# Classic-Narrow-5V-SIDE-USB.net
KiCad netlist of a schematic drawn in EAGLE
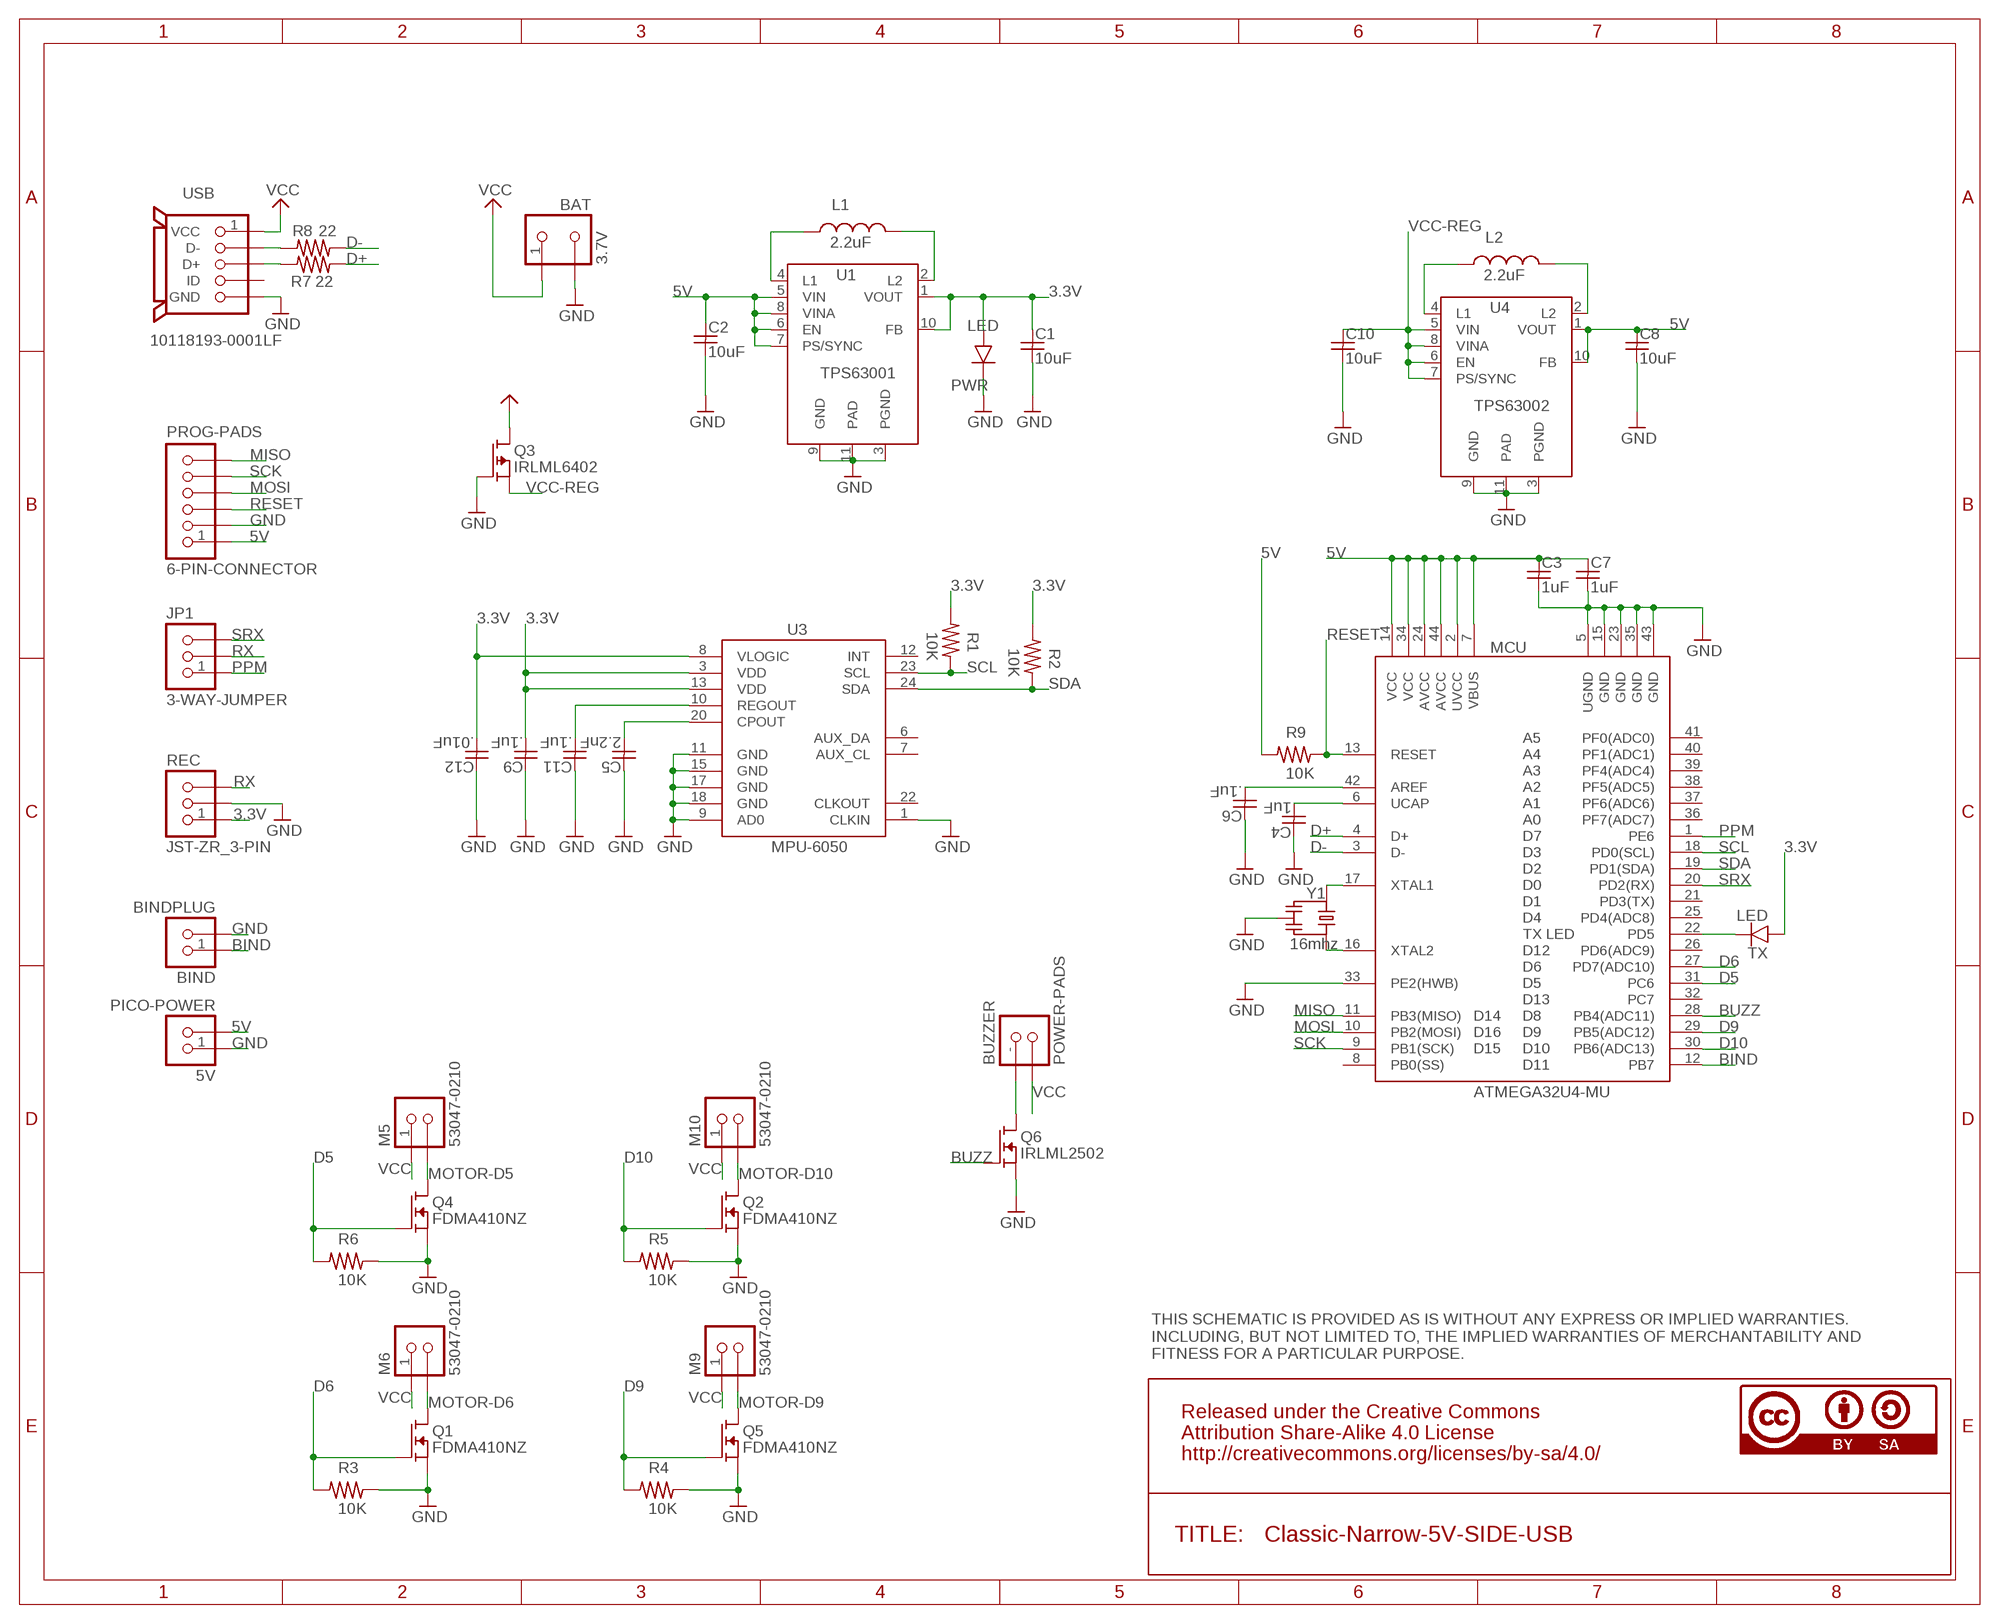
[diagram p0: schematic, sheet 1]

(export (version "E")
  (design (tool "Eeschema 10.0.6"))
  (components
    (comp (ref "5V")
      (value "PICO-POWER")
      (footprint "eagle-import:PICO_1.25_.5MM")
      (fields (field (name "MF") "Molex") (field (name "MPN") "53047-0210"))
      (libsource (lib "eagle-import") (part "PICO-POWER"))
    )
    (comp (ref "BAT")
      (value "3.7V")
      (footprint "eagle-import:S2B-PH-K-S")
      (fields (field (name "MF") "JST") (field (name "MPN") "S2B-PH-K-S"))
      (libsource (lib "eagle-import") (part "JST-PH-BAT"))
    )
    (comp (ref "BIND")
      (value "BINDPLUG")
      (footprint "eagle-import:B3U-1000P(M)")
      (fields (field (name "MF") "Omron") (field (name "MPN") "B3U-1000P"))
      (libsource (lib "eagle-import") (part "TACTILE-SWITCH"))
    )
    (comp (ref "BUZZER")
      (value "POWER-PADS")
      (footprint "eagle-import:POW-PADS")
      (libsource (lib "eagle-import") (part "POWER-PADS"))
    )
    (comp (ref "C1")
      (value "10uF")
      (footprint "eagle-import:YUDEN-CAP-0805")
      (fields (field (name "MF") "Taiyo Yuden") (field (name "MPN") "JMK212AB7106KG-T"))
      (libsource (lib "eagle-import") (part "CAPACITOR10UF"))
    )
    (comp (ref "C2")
      (value "10uF")
      (footprint "eagle-import:YUDEN-CAP-0805")
      (fields (field (name "MF") "Taiyo Yuden") (field (name "MPN") "JMK212AB7106KG-T"))
      (libsource (lib "eagle-import") (part "CAPACITOR10UF"))
    )
    (comp (ref "C3")
      (value "1uF")
      (footprint "eagle-import:MUR-CAP-0603")
      (fields (field (name "MF") "Murata") (field (name "MPN") "GRM188R71C105KA12D"))
      (libsource (lib "eagle-import") (part "CAPACITOR1UF"))
    )
    (comp (ref "C4")
      (value "1uF")
      (footprint "eagle-import:MUR-CAP-0603")
      (fields (field (name "MF") "Murata") (field (name "MPN") "GRM188R71C105KA12D"))
      (libsource (lib "eagle-import") (part "CAPACITOR1UF"))
    )
    (comp (ref "C5")
      (value "2.2nF")
      (footprint "eagle-import:MUR-CAP-0603")
      (fields (field (name "MF") "Murata") (field (name "MPN") "GRM188R71C222KA01D"))
      (libsource (lib "eagle-import") (part "CAPACITOR2.2NF"))
    )
    (comp (ref "C6")
      (value ".1uF")
      (footprint "eagle-import:MUR-CAP-0603")
      (fields (field (name "MF") "Murata") (field (name "MPN") "GRM188R71C104KA01D"))
      (libsource (lib "eagle-import") (part "CAPACITOR.1UF"))
    )
    (comp (ref "C7")
      (value "1uF")
      (footprint "eagle-import:MUR-CAP-0603")
      (fields (field (name "MF") "Murata") (field (name "MPN") "GRM188R71C105KA12D"))
      (libsource (lib "eagle-import") (part "CAPACITOR1UF"))
    )
    (comp (ref "C8")
      (value "10uF")
      (footprint "eagle-import:YUDEN-CAP-0805")
      (fields (field (name "MF") "Taiyo Yuden") (field (name "MPN") "JMK212AB7106KG-T"))
      (libsource (lib "eagle-import") (part "CAPACITOR10UF"))
    )
    (comp (ref "C9")
      (value ".1uF")
      (footprint "eagle-import:MUR-CAP-0603")
      (fields (field (name "MF") "Murata") (field (name "MPN") "GRM188R71C104KA01D"))
      (libsource (lib "eagle-import") (part "CAPACITOR.1UF"))
    )
    (comp (ref "C10")
      (value "10uF")
      (footprint "eagle-import:YUDEN-CAP-0805")
      (fields (field (name "MF") "Taiyo Yuden") (field (name "MPN") "JMK212AB7106KG-T"))
      (libsource (lib "eagle-import") (part "CAPACITOR10UF"))
    )
    (comp (ref "C11")
      (value ".1uF")
      (footprint "eagle-import:MUR-CAP-0603")
      (fields (field (name "MF") "Murata") (field (name "MPN") "GRM188R71C104KA01D"))
      (libsource (lib "eagle-import") (part "CAPACITOR.1UF"))
    )
    (comp (ref "C12")
      (value ".01uF")
      (footprint "eagle-import:MUR-CAP-0603")
      (fields (field (name "MF") "Murata") (field (name "MPN") "GRM188R71C103KA01D"))
      (libsource (lib "eagle-import") (part "CAPACITOR.01UF"))
    )
    (comp (ref "JP1")
      (value "3-WAY-JUMPER")
      (footprint "eagle-import:3-WAY-JUMPER")
      (libsource (lib "eagle-import") (part "3-WAY-JUMPER"))
    )
    (comp (ref "L1")
      (value "2.2uF")
      (footprint "eagle-import:NR301X")
      (fields (field (name "MF") "Taiyo Yuden") (field (name "MPN") "NR3015T2R2M"))
      (libsource (lib "eagle-import") (part "NR301X"))
    )
    (comp (ref "L2")
      (value "2.2uF")
      (footprint "eagle-import:NR301X")
      (fields (field (name "MF") "Taiyo Yuden") (field (name "MPN") "NR3015T2R2M"))
      (libsource (lib "eagle-import") (part "NR301X"))
    )
    (comp (ref "M5")
      (value "53047-0210")
      (footprint "eagle-import:PICO-53047-02")
      (fields (field (name "MF") "MOLEX"))
      (libsource (lib "eagle-import") (part "PICO-1.25-MOTOR"))
    )
    (comp (ref "M6")
      (value "53047-0210")
      (footprint "eagle-import:PICO-53047-02")
      (fields (field (name "MF") "MOLEX"))
      (libsource (lib "eagle-import") (part "PICO-1.25-MOTOR"))
    )
    (comp (ref "M9")
      (value "53047-0210")
      (footprint "eagle-import:PICO-53047-02")
      (fields (field (name "MF") "MOLEX"))
      (libsource (lib "eagle-import") (part "PICO-1.25-MOTOR"))
    )
    (comp (ref "M10")
      (value "53047-0210")
      (footprint "eagle-import:PICO-53047-02")
      (fields (field (name "MF") "MOLEX"))
      (libsource (lib "eagle-import") (part "PICO-1.25-MOTOR"))
    )
    (comp (ref "MCU")
      (value "ATMEGA32U4-MU")
      (footprint "eagle-import:QFN44-7X7")
      (fields (field (name "MF") "Atmel") (field (name "MPN") "Atmega32U4-MU"))
      (libsource (lib "eagle-import") (part "ATMEGA32U4-MU"))
    )
    (comp (ref "PROG-PADS")
      (value "6-PIN-CONNECTOR")
      (footprint "eagle-import:B6B-ZR")
      (fields (field (name "MF") "JST") (field (name "MPN") "B6B-ZR(LF)(SN)"))
      (libsource (lib "eagle-import") (part "6-PIN-CONNECTOR"))
    )
    (comp (ref "PWR")
      (value "LED")
      (footprint "eagle-import:SMD-CHIP-LED-0805")
      (fields (field (name "MF") "Kingbright") (field (name "MPN") "APHCM2012QBC/D-F01"))
      (libsource (lib "eagle-import") (part "SMD-CHIP-LED-0805"))
    )
    (comp (ref "Q1")
      (value "FDMA410NZ")
      (footprint "eagle-import:MICROFET-2X2")
      (fields (field (name "MF") "Fairchild"))
      (libsource (lib "eagle-import") (part "FDMA410NZ"))
    )
    (comp (ref "Q2")
      (value "FDMA410NZ")
      (footprint "eagle-import:MICROFET-2X2")
      (fields (field (name "MF") "Fairchild"))
      (libsource (lib "eagle-import") (part "FDMA410NZ"))
    )
    (comp (ref "Q3")
      (value "IRLML6402")
      (footprint "eagle-import:SOT-23")
      (fields (field (name "MF") "IR"))
      (libsource (lib "eagle-import") (part "MOSFET-P"))
    )
    (comp (ref "Q4")
      (value "FDMA410NZ")
      (footprint "eagle-import:MICROFET-2X2")
      (fields (field (name "MF") "Fairchild"))
      (libsource (lib "eagle-import") (part "FDMA410NZ"))
    )
    (comp (ref "Q5")
      (value "FDMA410NZ")
      (footprint "eagle-import:MICROFET-2X2")
      (fields (field (name "MF") "Fairchild"))
      (libsource (lib "eagle-import") (part "FDMA410NZ"))
    )
    (comp (ref "Q6")
      (value "IRLML2502")
      (footprint "eagle-import:SOT-23")
      (fields (field (name "MF") "IR"))
      (libsource (lib "eagle-import") (part "MOSFET-N2502"))
    )
    (comp (ref "R1")
      (value "10K")
      (footprint "eagle-import:VISH-RES-0603")
      (fields (field (name "MF") "Vishay") (field (name "MPN") "CRCW060310K0FKEAHP"))
      (libsource (lib "eagle-import") (part "RESISTOR10K"))
    )
    (comp (ref "R2")
      (value "10K")
      (footprint "eagle-import:VISH-RES-0603")
      (fields (field (name "MF") "Vishay") (field (name "MPN") "CRCW060310K0FKEAHP"))
      (libsource (lib "eagle-import") (part "RESISTOR10K"))
    )
    (comp (ref "R3")
      (value "10K")
      (footprint "eagle-import:VISH-RES-0603")
      (fields (field (name "MF") "Vishay") (field (name "MPN") "CRCW060310K0FKEAHP"))
      (libsource (lib "eagle-import") (part "RESISTOR10K"))
    )
    (comp (ref "R4")
      (value "10K")
      (footprint "eagle-import:VISH-RES-0603")
      (fields (field (name "MF") "Vishay") (field (name "MPN") "CRCW060310K0FKEAHP"))
      (libsource (lib "eagle-import") (part "RESISTOR10K"))
    )
    (comp (ref "R5")
      (value "10K")
      (footprint "eagle-import:VISH-RES-0603")
      (fields (field (name "MF") "Vishay") (field (name "MPN") "CRCW060310K0FKEAHP"))
      (libsource (lib "eagle-import") (part "RESISTOR10K"))
    )
    (comp (ref "R6")
      (value "10K")
      (footprint "eagle-import:VISH-RES-0603")
      (fields (field (name "MF") "Vishay") (field (name "MPN") "CRCW060310K0FKEAHP"))
      (libsource (lib "eagle-import") (part "RESISTOR10K"))
    )
    (comp (ref "R7")
      (value "22")
      (footprint "eagle-import:VISH-RES-0603")
      (fields (field (name "MF") "Vishay") (field (name "MPN") "CRCW060322R0FKEAHP"))
      (libsource (lib "eagle-import") (part "RESISTOR22"))
    )
    (comp (ref "R8")
      (value "22")
      (footprint "eagle-import:VISH-RES-0603")
      (fields (field (name "MF") "Vishay") (field (name "MPN") "CRCW060322R0FKEAHP"))
      (libsource (lib "eagle-import") (part "RESISTOR22"))
    )
    (comp (ref "R9")
      (value "10K")
      (footprint "eagle-import:VISH-RES-0603")
      (fields (field (name "MF") "Vishay") (field (name "MPN") "CRCW060310K0FKEAHP"))
      (libsource (lib "eagle-import") (part "RESISTOR10K"))
    )
    (comp (ref "REC")
      (value "JST-ZR_3-PIN")
      (footprint "eagle-import:S3B-ZR")
      (fields (field (name "MF") "JST") (field (name "MPN") "S3B-ZR"))
      (libsource (lib "eagle-import") (part "JST-ZR_3-PIN"))
    )
    (comp (ref "TX")
      (value "LED")
      (footprint "eagle-import:SMD-CHIP-LED-0805")
      (fields (field (name "MF") "Kingbright") (field (name "MPN") "APHCM2012QBC/D-F01"))
      (libsource (lib "eagle-import") (part "SMD-CHIP-LED-0805"))
    )
    (comp (ref "U1")
      (value "TPS63001")
      (footprint "eagle-import:VSON-N10")
      (fields (field (name "MF") "TI") (field (name "MPN") "TPS63001DRCR"))
      (libsource (lib "eagle-import") (part "TPS630XX-TPS63001"))
    )
    (comp (ref "U3")
      (value "MPU-6050")
      (footprint "eagle-import:QFN24-4X4")
      (fields (field (name "MF") "Invensense"))
      (libsource (lib "eagle-import") (part "MPU-6050"))
    )
    (comp (ref "U4")
      (value "TPS63002")
      (footprint "eagle-import:VSON-N10")
      (fields (field (name "MF") "TI") (field (name "MPN") "TPS63002DRCR"))
      (libsource (lib "eagle-import") (part "TPS630XX-TPS63002"))
    )
    (comp (ref "USB")
      (value "10118193-0001LF")
      (footprint "eagle-import:10118193-0001LF")
      (fields (field (name "MF") "FCI"))
      (libsource (lib "eagle-import") (part "USB-MICRO-B-FCI"))
    )
    (comp (ref "Y1")
      (value "16mhz")
      (footprint "eagle-import:RESONATOR_16")
      (fields (field (name "MF") "Murata") (field (name "MPN") "CSTCE16M0V53-R0"))
      (libsource (lib "eagle-import") (part "RESONATOR16MHZ"))
    )
  )
  (nets
    (net (code "1") (name "/3.3V") (class "Default")
      (node (ref "C1") (pin "1") (pinfunction "1_1") (pintype "passive"))
      (node (ref "C12") (pin "2") (pinfunction "2_2") (pintype "passive"))
      (node (ref "C9") (pin "2") (pinfunction "2_2") (pintype "passive"))
      (node (ref "PWR") (pin "A") (pinfunction "A_A") (pintype "passive"))
      (node (ref "R1") (pin "2") (pinfunction "2_2") (pintype "passive"))
      (node (ref "R2") (pin "2") (pinfunction "2_2") (pintype "passive"))
      (node (ref "REC") (pin "1") (pinfunction "1_1") (pintype "bidirectional"))
      (node (ref "TX") (pin "A") (pinfunction "A_A") (pintype "passive"))
      (node (ref "U1") (pin "1") (pinfunction "VOUT_1") (pintype "bidirectional"))
      (node (ref "U1") (pin "10") (pinfunction "FB_10") (pintype "bidirectional"))
      (node (ref "U3") (pin "13") (pinfunction "VDD_13") (pintype "bidirectional"))
      (node (ref "U3") (pin "3") (pinfunction "VDD_3") (pintype "bidirectional"))
      (node (ref "U3") (pin "8") (pinfunction "VLOGIC_8") (pintype "bidirectional"))
    )
    (net (code "2") (name "/5V") (class "Default")
      (node (ref "5V") (pin "2") (pinfunction "2_2") (pintype "passive"))
      (node (ref "C2") (pin "1") (pinfunction "1_1") (pintype "passive"))
      (node (ref "C3") (pin "1") (pinfunction "1_1") (pintype "passive"))
      (node (ref "C7") (pin "1") (pinfunction "1_1") (pintype "passive"))
      (node (ref "C8") (pin "1") (pinfunction "1_1") (pintype "passive"))
      (node (ref "MCU") (pin "14") (pinfunction "VCC_14") (pintype "bidirectional"))
      (node (ref "MCU") (pin "2") (pinfunction "UVCC_2") (pintype "bidirectional"))
      (node (ref "MCU") (pin "24") (pinfunction "AVCC_24") (pintype "bidirectional"))
      (node (ref "MCU") (pin "34") (pinfunction "VCC_34") (pintype "bidirectional"))
      (node (ref "MCU") (pin "44") (pinfunction "AVCC_44") (pintype "bidirectional"))
      (node (ref "MCU") (pin "7") (pinfunction "VBUS_7") (pintype "bidirectional"))
      (node (ref "PROG-PADS") (pin "1") (pinfunction "1_1") (pintype "bidirectional"))
      (node (ref "R9") (pin "2") (pinfunction "2_2") (pintype "passive"))
      (node (ref "U1") (pin "5") (pinfunction "VIN_5") (pintype "bidirectional"))
      (node (ref "U1") (pin "6") (pinfunction "EN_6") (pintype "bidirectional"))
      (node (ref "U1") (pin "7") (pinfunction "PS/SYNC_7") (pintype "bidirectional"))
      (node (ref "U1") (pin "8") (pinfunction "VINA_8") (pintype "bidirectional"))
      (node (ref "U4") (pin "1") (pinfunction "VOUT_1") (pintype "bidirectional"))
      (node (ref "U4") (pin "10") (pinfunction "FB_10") (pintype "bidirectional"))
    )
    (net (code "3") (name "/BIND") (class "Default")
      (node (ref "BIND") (pin "1") (pinfunction "1_1") (pintype "passive"))
      (node (ref "MCU") (pin "12") (pinfunction "PB7_12") (pintype "bidirectional"))
    )
    (net (code "4") (name "/BUZZ") (class "Default")
      (node (ref "MCU") (pin "28") (pinfunction "PB4(ADC11)_28") (pintype "bidirectional"))
      (node (ref "Q6") (pin "1") (pinfunction "G_1") (pintype "bidirectional"))
    )
    (net (code "5") (name "/D+") (class "Default")
      (node (ref "MCU") (pin "4") (pinfunction "D+_4") (pintype "bidirectional"))
      (node (ref "R7") (pin "1") (pinfunction "1_1") (pintype "passive"))
    )
    (net (code "6") (name "/D-") (class "Default")
      (node (ref "MCU") (pin "3") (pinfunction "D-_3") (pintype "bidirectional"))
      (node (ref "R8") (pin "1") (pinfunction "1_1") (pintype "passive"))
    )
    (net (code "7") (name "/D5") (class "Default")
      (node (ref "MCU") (pin "31") (pinfunction "PC6_31") (pintype "bidirectional"))
      (node (ref "Q4") (pin "G") (pinfunction "G_G") (pintype "bidirectional"))
      (node (ref "R6") (pin "2") (pinfunction "2_2") (pintype "passive"))
    )
    (net (code "8") (name "/D6") (class "Default")
      (node (ref "MCU") (pin "27") (pinfunction "PD7(ADC10)_27") (pintype "bidirectional"))
      (node (ref "Q1") (pin "G") (pinfunction "G_G") (pintype "bidirectional"))
      (node (ref "R3") (pin "2") (pinfunction "2_2") (pintype "passive"))
    )
    (net (code "9") (name "/D9") (class "Default")
      (node (ref "MCU") (pin "29") (pinfunction "PB5(ADC12)_29") (pintype "bidirectional"))
      (node (ref "Q5") (pin "G") (pinfunction "G_G") (pintype "bidirectional"))
      (node (ref "R4") (pin "2") (pinfunction "2_2") (pintype "passive"))
    )
    (net (code "10") (name "/D10") (class "Default")
      (node (ref "MCU") (pin "30") (pinfunction "PB6(ADC13)_30") (pintype "bidirectional"))
      (node (ref "Q2") (pin "G") (pinfunction "G_G") (pintype "bidirectional"))
      (node (ref "R5") (pin "2") (pinfunction "2_2") (pintype "passive"))
    )
    (net (code "11") (name "/MISO") (class "Default")
      (node (ref "MCU") (pin "11") (pinfunction "PB3(MISO)_11") (pintype "bidirectional"))
      (node (ref "PROG-PADS") (pin "6") (pinfunction "6_6") (pintype "bidirectional"))
    )
    (net (code "12") (name "/MOSI") (class "Default")
      (node (ref "MCU") (pin "10") (pinfunction "PB2(MOSI)_10") (pintype "bidirectional"))
      (node (ref "PROG-PADS") (pin "4") (pinfunction "4_4") (pintype "bidirectional"))
    )
    (net (code "13") (name "/MOTOR-D5") (class "Default")
      (node (ref "M5") (pin "2") (pinfunction "2_2") (pintype "passive"))
      (node (ref "Q4") (pin "D") (pinfunction "D_D") (pintype "bidirectional"))
      (node (ref "Q4") (pin "D1") (pinfunction "D_D1") (pintype "bidirectional"))
      (node (ref "Q4") (pin "D2") (pinfunction "D_D2") (pintype "bidirectional"))
      (node (ref "Q4") (pin "D3") (pinfunction "D_D3") (pintype "bidirectional"))
      (node (ref "Q4") (pin "D4") (pinfunction "D_D4") (pintype "bidirectional"))
    )
    (net (code "14") (name "/MOTOR-D6") (class "Default")
      (node (ref "M6") (pin "2") (pinfunction "2_2") (pintype "passive"))
      (node (ref "Q1") (pin "D") (pinfunction "D_D") (pintype "bidirectional"))
      (node (ref "Q1") (pin "D1") (pinfunction "D_D1") (pintype "bidirectional"))
      (node (ref "Q1") (pin "D2") (pinfunction "D_D2") (pintype "bidirectional"))
      (node (ref "Q1") (pin "D3") (pinfunction "D_D3") (pintype "bidirectional"))
      (node (ref "Q1") (pin "D4") (pinfunction "D_D4") (pintype "bidirectional"))
    )
    (net (code "15") (name "/MOTOR-D9") (class "Default")
      (node (ref "M9") (pin "2") (pinfunction "2_2") (pintype "passive"))
      (node (ref "Q5") (pin "D") (pinfunction "D_D") (pintype "bidirectional"))
      (node (ref "Q5") (pin "D1") (pinfunction "D_D1") (pintype "bidirectional"))
      (node (ref "Q5") (pin "D2") (pinfunction "D_D2") (pintype "bidirectional"))
      (node (ref "Q5") (pin "D3") (pinfunction "D_D3") (pintype "bidirectional"))
      (node (ref "Q5") (pin "D4") (pinfunction "D_D4") (pintype "bidirectional"))
    )
    (net (code "16") (name "/MOTOR-D10") (class "Default")
      (node (ref "M10") (pin "2") (pinfunction "2_2") (pintype "passive"))
      (node (ref "Q2") (pin "D") (pinfunction "D_D") (pintype "bidirectional"))
      (node (ref "Q2") (pin "D1") (pinfunction "D_D1") (pintype "bidirectional"))
      (node (ref "Q2") (pin "D2") (pinfunction "D_D2") (pintype "bidirectional"))
      (node (ref "Q2") (pin "D3") (pinfunction "D_D3") (pintype "bidirectional"))
      (node (ref "Q2") (pin "D4") (pinfunction "D_D4") (pintype "bidirectional"))
    )
    (net (code "17") (name "/PPM") (class "Default")
      (node (ref "JP1") (pin "1") (pinfunction "1_1") (pintype "bidirectional"))
      (node (ref "MCU") (pin "1") (pinfunction "PE6_1") (pintype "bidirectional"))
    )
    (net (code "18") (name "/RESET") (class "Default")
      (node (ref "MCU") (pin "13") (pinfunction "RESET_13") (pintype "bidirectional"))
      (node (ref "PROG-PADS") (pin "3") (pinfunction "3_3") (pintype "bidirectional"))
      (node (ref "R9") (pin "1") (pinfunction "1_1") (pintype "passive"))
    )
    (net (code "19") (name "/RX") (class "Default")
      (node (ref "JP1") (pin "2") (pinfunction "2_2") (pintype "bidirectional"))
      (node (ref "REC") (pin "3") (pinfunction "3_3") (pintype "bidirectional"))
    )
    (net (code "20") (name "/SCK") (class "Default")
      (node (ref "MCU") (pin "9") (pinfunction "PB1(SCK)_9") (pintype "bidirectional"))
      (node (ref "PROG-PADS") (pin "5") (pinfunction "5_5") (pintype "bidirectional"))
    )
    (net (code "21") (name "/SCL") (class "Default")
      (node (ref "MCU") (pin "18") (pinfunction "PD0(SCL)_18") (pintype "bidirectional"))
      (node (ref "R1") (pin "1") (pinfunction "1_1") (pintype "passive"))
      (node (ref "U3") (pin "23") (pinfunction "SCL_23") (pintype "bidirectional"))
    )
    (net (code "22") (name "/SDA") (class "Default")
      (node (ref "MCU") (pin "19") (pinfunction "PD1(SDA)_19") (pintype "bidirectional"))
      (node (ref "R2") (pin "1") (pinfunction "1_1") (pintype "passive"))
      (node (ref "U3") (pin "24") (pinfunction "SDA_24") (pintype "bidirectional"))
    )
    (net (code "23") (name "/SRX") (class "Default")
      (node (ref "JP1") (pin "3") (pinfunction "3_3") (pintype "bidirectional"))
      (node (ref "MCU") (pin "20") (pinfunction "PD2(RX)_20") (pintype "bidirectional"))
    )
    (net (code "24") (name "/VCC-REG") (class "Default")
      (node (ref "C10") (pin "1") (pinfunction "1_1") (pintype "passive"))
      (node (ref "Q3") (pin "2") (pinfunction "S_2") (pintype "bidirectional"))
      (node (ref "U4") (pin "5") (pinfunction "VIN_5") (pintype "bidirectional"))
      (node (ref "U4") (pin "6") (pinfunction "EN_6") (pintype "bidirectional"))
      (node (ref "U4") (pin "7") (pinfunction "PS/SYNC_7") (pintype "bidirectional"))
      (node (ref "U4") (pin "8") (pinfunction "VINA_8") (pintype "bidirectional"))
    )
    (net (code "25") (name "GND") (class "Default")
      (node (ref "5V") (pin "1") (pinfunction "1_1") (pintype "passive"))
      (node (ref "BAT") (pin "2") (pinfunction "2_2") (pintype "bidirectional"))
      (node (ref "BIND") (pin "2") (pinfunction "2_2") (pintype "passive"))
      (node (ref "C1") (pin "2") (pinfunction "2_2") (pintype "passive"))
      (node (ref "C10") (pin "2") (pinfunction "2_2") (pintype "passive"))
      (node (ref "C11") (pin "1") (pinfunction "1_1") (pintype "passive"))
      (node (ref "C12") (pin "1") (pinfunction "1_1") (pintype "passive"))
      (node (ref "C2") (pin "2") (pinfunction "2_2") (pintype "passive"))
      (node (ref "C3") (pin "2") (pinfunction "2_2") (pintype "passive"))
      (node (ref "C4") (pin "1") (pinfunction "1_1") (pintype "passive"))
      (node (ref "C5") (pin "1") (pinfunction "1_1") (pintype "passive"))
      (node (ref "C6") (pin "1") (pinfunction "1_1") (pintype "passive"))
      (node (ref "C7") (pin "2") (pinfunction "2_2") (pintype "passive"))
      (node (ref "C8") (pin "2") (pinfunction "2_2") (pintype "passive"))
      (node (ref "C9") (pin "1") (pinfunction "1_1") (pintype "passive"))
      (node (ref "MCU") (pin "15") (pinfunction "GND_15") (pintype "bidirectional"))
      (node (ref "MCU") (pin "23") (pinfunction "GND_23") (pintype "bidirectional"))
      (node (ref "MCU") (pin "33") (pinfunction "PE2(HWB)_33") (pintype "bidirectional"))
      (node (ref "MCU") (pin "35") (pinfunction "GND_35") (pintype "bidirectional"))
      (node (ref "MCU") (pin "43") (pinfunction "GND_43") (pintype "bidirectional"))
      (node (ref "MCU") (pin "5") (pinfunction "UGND_5") (pintype "bidirectional"))
      (node (ref "PROG-PADS") (pin "2") (pinfunction "2_2") (pintype "bidirectional"))
      (node (ref "PWR") (pin "C") (pinfunction "C_C") (pintype "passive"))
      (node (ref "Q1") (pin "S") (pinfunction "S_S") (pintype "bidirectional"))
      (node (ref "Q1") (pin "S1") (pinfunction "S_S1") (pintype "bidirectional"))
      (node (ref "Q2") (pin "S") (pinfunction "S_S") (pintype "bidirectional"))
      (node (ref "Q2") (pin "S1") (pinfunction "S_S1") (pintype "bidirectional"))
      (node (ref "Q3") (pin "1") (pinfunction "G_1") (pintype "bidirectional"))
      (node (ref "Q4") (pin "S") (pinfunction "S_S") (pintype "bidirectional"))
      (node (ref "Q4") (pin "S1") (pinfunction "S_S1") (pintype "bidirectional"))
      (node (ref "Q5") (pin "S") (pinfunction "S_S") (pintype "bidirectional"))
      (node (ref "Q5") (pin "S1") (pinfunction "S_S1") (pintype "bidirectional"))
      (node (ref "Q6") (pin "2") (pinfunction "S_2") (pintype "bidirectional"))
      (node (ref "R3") (pin "1") (pinfunction "1_1") (pintype "passive"))
      (node (ref "R4") (pin "1") (pinfunction "1_1") (pintype "passive"))
      (node (ref "R5") (pin "1") (pinfunction "1_1") (pintype "passive"))
      (node (ref "R6") (pin "1") (pinfunction "1_1") (pintype "passive"))
      (node (ref "REC") (pin "2") (pinfunction "2_2") (pintype "bidirectional"))
      (node (ref "U1") (pin "11") (pinfunction "PAD_11") (pintype "bidirectional"))
      (node (ref "U1") (pin "3") (pinfunction "PGND_3") (pintype "bidirectional"))
      (node (ref "U1") (pin "9") (pinfunction "GND_9") (pintype "bidirectional"))
      (node (ref "U3") (pin "1") (pinfunction "CLKIN_1") (pintype "bidirectional"))
      (node (ref "U3") (pin "11") (pinfunction "GND_11") (pintype "bidirectional"))
      (node (ref "U3") (pin "15") (pinfunction "GND_15") (pintype "bidirectional"))
      (node (ref "U3") (pin "17") (pinfunction "GND_17") (pintype "bidirectional"))
      (node (ref "U3") (pin "18") (pinfunction "GND_18") (pintype "bidirectional"))
      (node (ref "U3") (pin "9") (pinfunction "AD0_9") (pintype "bidirectional"))
      (node (ref "U4") (pin "11") (pinfunction "PAD_11") (pintype "bidirectional"))
      (node (ref "U4") (pin "3") (pinfunction "PGND_3") (pintype "bidirectional"))
      (node (ref "U4") (pin "9") (pinfunction "GND_9") (pintype "bidirectional"))
      (node (ref "USB") (pin "5") (pinfunction "GND_5") (pintype "passive"))
      (node (ref "USB") (pin "GND") (pinfunction "GND_GND") (pintype "passive"))
      (node (ref "USB") (pin "GND2") (pinfunction "GND_GND2") (pintype "passive"))
      (node (ref "USB") (pin "HOLE1") (pinfunction "GND_HOLE1") (pintype "passive"))
      (node (ref "USB") (pin "HOLE2") (pinfunction "GND_HOLE2") (pintype "passive"))
      (node (ref "Y1") (pin "2") (pinfunction "2_2") (pintype "passive"))
    )
    (net (code "26") (name "Net-(BUZZER-1)") (class "Default")
      (node (ref "BUZZER") (pin "-") (pinfunction "1_-") (pintype "passive"))
      (node (ref "Q6") (pin "3") (pinfunction "D_3") (pintype "bidirectional"))
    )
    (net (code "27") (name "Net-(MCU-AREF)") (class "Default")
      (node (ref "C6") (pin "2") (pinfunction "2_2") (pintype "passive"))
      (node (ref "MCU") (pin "42") (pinfunction "AREF_42") (pintype "bidirectional"))
    )
    (net (code "28") (name "Net-(MCU-PD5)") (class "Default")
      (node (ref "MCU") (pin "22") (pinfunction "PD5_22") (pintype "bidirectional"))
      (node (ref "TX") (pin "C") (pinfunction "C_C") (pintype "passive"))
    )
    (net (code "29") (name "Net-(MCU-UCAP)") (class "Default")
      (node (ref "C4") (pin "2") (pinfunction "2_2") (pintype "passive"))
      (node (ref "MCU") (pin "6") (pinfunction "UCAP_6") (pintype "bidirectional"))
    )
    (net (code "30") (name "Net-(MCU-XTAL1)") (class "Default")
      (node (ref "MCU") (pin "17") (pinfunction "XTAL1_17") (pintype "bidirectional"))
      (node (ref "Y1") (pin "1") (pinfunction "1_1") (pintype "passive"))
    )
    (net (code "31") (name "Net-(MCU-XTAL2)") (class "Default")
      (node (ref "MCU") (pin "16") (pinfunction "XTAL2_16") (pintype "bidirectional"))
      (node (ref "Y1") (pin "3") (pinfunction "3_3") (pintype "passive"))
    )
    (net (code "32") (name "Net-(U1-L1)") (class "Default")
      (node (ref "L1") (pin "1") (pinfunction "1_1") (pintype "passive"))
      (node (ref "U1") (pin "4") (pinfunction "L1_4") (pintype "bidirectional"))
    )
    (net (code "33") (name "Net-(U1-L2)") (class "Default")
      (node (ref "L1") (pin "2") (pinfunction "2_2") (pintype "passive"))
      (node (ref "U1") (pin "2") (pinfunction "L2_2") (pintype "bidirectional"))
    )
    (net (code "34") (name "Net-(U3-CPOUT)") (class "Default")
      (node (ref "C5") (pin "2") (pinfunction "2_2") (pintype "passive"))
      (node (ref "U3") (pin "20") (pinfunction "CPOUT_20") (pintype "bidirectional"))
    )
    (net (code "35") (name "Net-(U3-REGOUT)") (class "Default")
      (node (ref "C11") (pin "2") (pinfunction "2_2") (pintype "passive"))
      (node (ref "U3") (pin "10") (pinfunction "REGOUT_10") (pintype "bidirectional"))
    )
    (net (code "36") (name "Net-(U4-L1)") (class "Default")
      (node (ref "L2") (pin "1") (pinfunction "1_1") (pintype "passive"))
      (node (ref "U4") (pin "4") (pinfunction "L1_4") (pintype "bidirectional"))
    )
    (net (code "37") (name "Net-(U4-L2)") (class "Default")
      (node (ref "L2") (pin "2") (pinfunction "2_2") (pintype "passive"))
      (node (ref "U4") (pin "2") (pinfunction "L2_2") (pintype "bidirectional"))
    )
    (net (code "38") (name "Net-(USB-D+)") (class "Default")
      (node (ref "R7") (pin "2") (pinfunction "2_2") (pintype "passive"))
      (node (ref "USB") (pin "3") (pinfunction "D+_3") (pintype "passive"))
    )
    (net (code "39") (name "Net-(USB-D-)") (class "Default")
      (node (ref "R8") (pin "2") (pinfunction "2_2") (pintype "passive"))
      (node (ref "USB") (pin "2") (pinfunction "D-_2") (pintype "passive"))
    )
    (net (code "40") (name "VCC") (class "Default")
      (node (ref "BAT") (pin "1") (pinfunction "1_1") (pintype "bidirectional"))
      (node (ref "BUZZER") (pin "+") (pinfunction "2_+") (pintype "passive"))
      (node (ref "M10") (pin "1") (pinfunction "1_1") (pintype "passive"))
      (node (ref "M5") (pin "1") (pinfunction "1_1") (pintype "passive"))
      (node (ref "M6") (pin "1") (pinfunction "1_1") (pintype "passive"))
      (node (ref "M9") (pin "1") (pinfunction "1_1") (pintype "passive"))
      (node (ref "Q3") (pin "3") (pinfunction "D_3") (pintype "bidirectional"))
      (node (ref "USB") (pin "1") (pinfunction "VCC_1") (pintype "passive"))
    )
    (net (code "41") (name "unconnected-(MCU-PB0(SS)-Pad8)") (class "Default")
      (node (ref "MCU") (pin "8") (pinfunction "PB0(SS)_8") (pintype "bidirectional"))
    )
    (net (code "42") (name "unconnected-(MCU-PC7-Pad32)") (class "Default")
      (node (ref "MCU") (pin "32") (pinfunction "PC7_32") (pintype "bidirectional"))
    )
    (net (code "43") (name "unconnected-(MCU-PD3(TX)-Pad21)") (class "Default")
      (node (ref "MCU") (pin "21") (pinfunction "PD3(TX)_21") (pintype "bidirectional"))
    )
    (net (code "44") (name "unconnected-(MCU-PD4(ADC8)-Pad25)") (class "Default")
      (node (ref "MCU") (pin "25") (pinfunction "PD4(ADC8)_25") (pintype "bidirectional"))
    )
    (net (code "45") (name "unconnected-(MCU-PD6(ADC9)-Pad26)") (class "Default")
      (node (ref "MCU") (pin "26") (pinfunction "PD6(ADC9)_26") (pintype "bidirectional"))
    )
    (net (code "46") (name "unconnected-(MCU-PF0(ADC0)-Pad41)") (class "Default")
      (node (ref "MCU") (pin "41") (pinfunction "PF0(ADC0)_41") (pintype "bidirectional"))
    )
    (net (code "47") (name "unconnected-(MCU-PF1(ADC1)-Pad40)") (class "Default")
      (node (ref "MCU") (pin "40") (pinfunction "PF1(ADC1)_40") (pintype "bidirectional"))
    )
    (net (code "48") (name "unconnected-(MCU-PF4(ADC4)-Pad39)") (class "Default")
      (node (ref "MCU") (pin "39") (pinfunction "PF4(ADC4)_39") (pintype "bidirectional"))
    )
    (net (code "49") (name "unconnected-(MCU-PF5(ADC5)-Pad38)") (class "Default")
      (node (ref "MCU") (pin "38") (pinfunction "PF5(ADC5)_38") (pintype "bidirectional"))
    )
    (net (code "50") (name "unconnected-(MCU-PF6(ADC6)-Pad37)") (class "Default")
      (node (ref "MCU") (pin "37") (pinfunction "PF6(ADC6)_37") (pintype "bidirectional"))
    )
    (net (code "51") (name "unconnected-(MCU-PF7(ADC7)-Pad36)") (class "Default")
      (node (ref "MCU") (pin "36") (pinfunction "PF7(ADC7)_36") (pintype "bidirectional"))
    )
    (net (code "52") (name "unconnected-(U3-AUX_CL-Pad7)") (class "Default")
      (node (ref "U3") (pin "7") (pinfunction "AUX_CL_7") (pintype "bidirectional"))
    )
    (net (code "53") (name "unconnected-(U3-AUX_DA-Pad6)") (class "Default")
      (node (ref "U3") (pin "6") (pinfunction "AUX_DA_6") (pintype "bidirectional"))
    )
    (net (code "54") (name "unconnected-(U3-CLKOUT-Pad22)") (class "Default")
      (node (ref "U3") (pin "22") (pinfunction "CLKOUT_22") (pintype "bidirectional"))
    )
    (net (code "55") (name "unconnected-(U3-INT-Pad12)") (class "Default")
      (node (ref "U3") (pin "12") (pinfunction "INT_12") (pintype "bidirectional"))
    )
    (net (code "56") (name "unconnected-(USB-ID-Pad4)") (class "Default")
      (node (ref "USB") (pin "4") (pinfunction "ID_4") (pintype "passive"))
    )
  )
)
